# Schematic_LED_Board.net
KiCad netlist of a schematic drawn in EAGLE
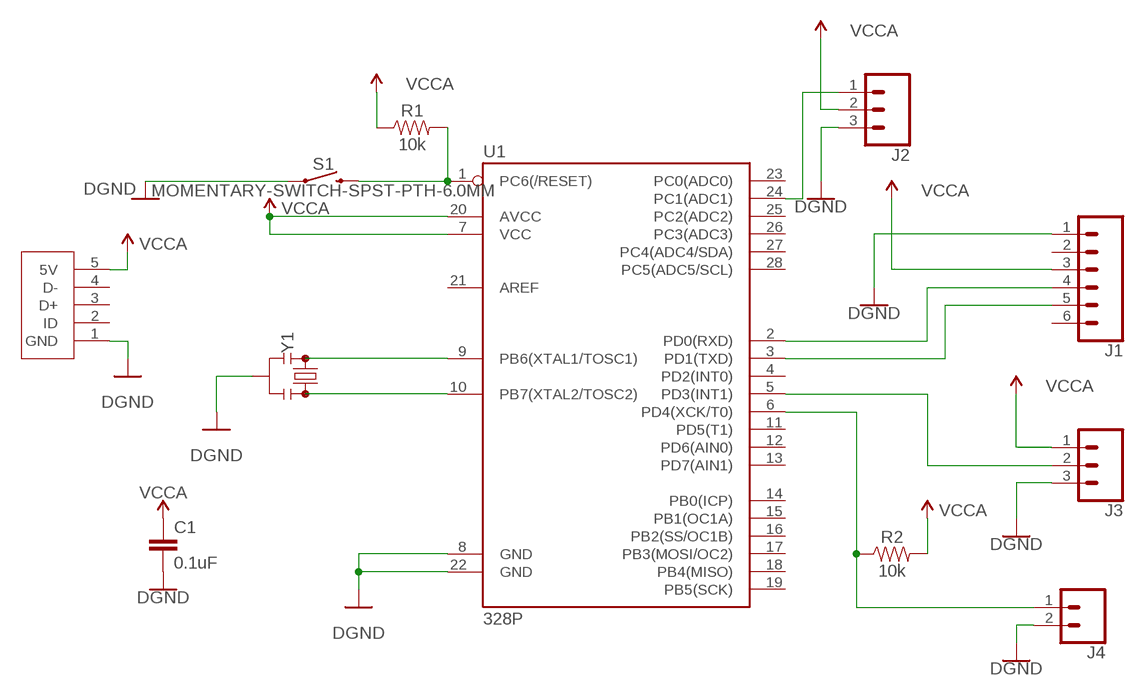
[diagram p0: schematic, sheet 1]

(export (version "E")
  (design (tool "Eeschema 10.0.6"))
  (components
    (comp (ref "C1")
      (value "0.1uF")
      (footprint "eagle-import:CAP-PTH-SMALL-KIT")
      (libsource (lib "eagle-import") (part "0.1UF-KIT-EZ-50V-20%"))
    )
    (comp (ref "J1")
      (value "CONN_06LONGPADS")
      (footprint "eagle-import:1X06_LONGPADS")
      (libsource (lib "eagle-import") (part "CONN_06LONGPADS"))
    )
    (comp (ref "J2")
      (value "CONN_03LONGPADS")
      (footprint "eagle-import:1X03_LONGPADS")
      (libsource (lib "eagle-import") (part "CONN_03LONGPADS"))
    )
    (comp (ref "J3")
      (value "CONN_03LONGPADS")
      (footprint "eagle-import:1X03_LONGPADS")
      (libsource (lib "eagle-import") (part "CONN_03LONGPADS"))
    )
    (comp (ref "J4")
      (value "CONN_02PTH3")
      (footprint "eagle-import:1X02_LONGPADS")
      (libsource (lib "eagle-import") (part "CONN_02PTH3"))
    )
    (comp (ref "R1")
      (value "10k")
      (footprint "eagle-import:AXIAL-0.3")
      (libsource (lib "eagle-import") (part "10KOHM-HORIZ-1/6W-5%"))
    )
    (comp (ref "R2")
      (value "10k")
      (footprint "eagle-import:AXIAL-0.3")
      (libsource (lib "eagle-import") (part "10KOHM-HORIZ-1/6W-5%"))
    )
    (comp (ref "S1")
      (value "MOMENTARY-SWITCH-SPST-PTH-6.0MM")
      (footprint "eagle-import:TACTILE_SWITCH_PTH_6.0MM")
      (libsource (lib "eagle-import") (part "MOMENTARY-SWITCH-SPST-PTH-6.0MM"))
    )
    (comp (ref "U$8")
      (value "USBPOWER")
      (footprint "eagle-import:1X05_LONGPADS")
      (libsource (lib "eagle-import") (part "USBPOWER"))
    )
    (comp (ref "U1")
      (value "328P")
      (footprint "eagle-import:DIP28")
      (libsource (lib "eagle-import") (part "ATMEGA328P_PDIP"))
    )
    (comp (ref "Y1")
      (value "RESONATORPTH-7.6X3.8")
      (footprint "eagle-import:RESONATOR-PTH-7.6X3.8")
      (libsource (lib "eagle-import") (part "RESONATORPTH-7.6X3.8"))
    )
  )
  (nets
    (net (code "1") (name "DGND") (class "Default")
      (node (ref "C1") (pin "2") (pinfunction "2_2") (pintype "passive"))
      (node (ref "J1") (pin "1") (pinfunction "1_1") (pintype "passive"))
      (node (ref "J2") (pin "3") (pinfunction "3_3") (pintype "passive"))
      (node (ref "J3") (pin "3") (pinfunction "3_3") (pintype "passive"))
      (node (ref "J4") (pin "2") (pinfunction "2_2") (pintype "passive"))
      (node (ref "S1") (pin "1") (pinfunction "1_1") (pintype "passive"))
      (node (ref "U$8") (pin "1") (pinfunction "GND_1") (pintype "bidirectional"))
      (node (ref "U1") (pin "22") (pinfunction "GND_22") (pintype "bidirectional"))
      (node (ref "U1") (pin "8") (pinfunction "GND_8") (pintype "bidirectional"))
      (node (ref "Y1") (pin "2") (pinfunction "2_2") (pintype "passive"))
    )
    (net (code "2") (name "Net-(R1-2)") (class "Default")
      (node (ref "R1") (pin "P$2") (pinfunction "2_P$2") (pintype "passive"))
      (node (ref "S1") (pin "3") (pinfunction "2_3") (pintype "passive"))
      (node (ref "U1") (pin "1") (pinfunction "PC6(/RESET)_1") (pintype "bidirectional"))
    )
    (net (code "3") (name "Net-(R2-1)") (class "Default")
      (node (ref "J4") (pin "1") (pinfunction "1_1") (pintype "passive"))
      (node (ref "R2") (pin "P$1") (pinfunction "1_P$1") (pintype "passive"))
      (node (ref "U1") (pin "6") (pinfunction "PD4(XCK/T0)_6") (pintype "bidirectional"))
    )
    (net (code "4") (name "Net-(U1-PB6(XTAL1{slash}TOSC1))") (class "Default")
      (node (ref "U1") (pin "9") (pinfunction "PB6(XTAL1/TOSC1)_9") (pintype "bidirectional"))
      (node (ref "Y1") (pin "1") (pinfunction "1_1") (pintype "passive"))
    )
    (net (code "5") (name "Net-(U1-PB7(XTAL2{slash}TOSC2))") (class "Default")
      (node (ref "U1") (pin "10") (pinfunction "PB7(XTAL2/TOSC2)_10") (pintype "bidirectional"))
      (node (ref "Y1") (pin "3") (pinfunction "3_3") (pintype "passive"))
    )
    (net (code "6") (name "Net-(U1-PC1(ADC1))") (class "Default")
      (node (ref "J2") (pin "1") (pinfunction "1_1") (pintype "passive"))
      (node (ref "U1") (pin "24") (pinfunction "PC1(ADC1)_24") (pintype "bidirectional"))
    )
    (net (code "7") (name "Net-(U1-PD0(RXD))") (class "Default")
      (node (ref "J1") (pin "4") (pinfunction "4_4") (pintype "passive"))
      (node (ref "U1") (pin "2") (pinfunction "PD0(RXD)_2") (pintype "bidirectional"))
    )
    (net (code "8") (name "Net-(U1-PD1(TXD))") (class "Default")
      (node (ref "J1") (pin "5") (pinfunction "5_5") (pintype "passive"))
      (node (ref "U1") (pin "3") (pinfunction "PD1(TXD)_3") (pintype "bidirectional"))
    )
    (net (code "9") (name "Net-(U1-PD3(INT1))") (class "Default")
      (node (ref "J3") (pin "2") (pinfunction "2_2") (pintype "passive"))
      (node (ref "U1") (pin "5") (pinfunction "PD3(INT1)_5") (pintype "bidirectional"))
    )
    (net (code "10") (name "VCCA") (class "Default")
      (node (ref "C1") (pin "1") (pinfunction "1_1") (pintype "passive"))
      (node (ref "J1") (pin "3") (pinfunction "3_3") (pintype "passive"))
      (node (ref "J2") (pin "2") (pinfunction "2_2") (pintype "passive"))
      (node (ref "J3") (pin "1") (pinfunction "1_1") (pintype "passive"))
      (node (ref "R1") (pin "P$1") (pinfunction "1_P$1") (pintype "passive"))
      (node (ref "R2") (pin "P$2") (pinfunction "2_P$2") (pintype "passive"))
      (node (ref "U$8") (pin "5") (pinfunction "5V_5") (pintype "bidirectional"))
      (node (ref "U1") (pin "20") (pinfunction "AVCC_20") (pintype "bidirectional"))
      (node (ref "U1") (pin "7") (pinfunction "VCC_7") (pintype "bidirectional"))
    )
    (net (code "11") (name "unconnected-(J1-Pad2)") (class "Default")
      (node (ref "J1") (pin "2") (pinfunction "2_2") (pintype "passive"))
    )
    (net (code "12") (name "unconnected-(J1-Pad6)") (class "Default")
      (node (ref "J1") (pin "6") (pinfunction "6_6") (pintype "passive"))
    )
    (net (code "13") (name "unconnected-(U$8-D+-Pad3)") (class "Default")
      (node (ref "U$8") (pin "3") (pinfunction "D+_3") (pintype "bidirectional"))
    )
    (net (code "14") (name "unconnected-(U$8-D--Pad4)") (class "Default")
      (node (ref "U$8") (pin "4") (pinfunction "D-_4") (pintype "bidirectional"))
    )
    (net (code "15") (name "unconnected-(U$8-ID-Pad2)") (class "Default")
      (node (ref "U$8") (pin "2") (pinfunction "ID_2") (pintype "bidirectional"))
    )
    (net (code "16") (name "unconnected-(U1-AREF-Pad21)") (class "Default")
      (node (ref "U1") (pin "21") (pinfunction "AREF_21") (pintype "bidirectional"))
    )
    (net (code "17") (name "unconnected-(U1-PB0(ICP)-Pad14)") (class "Default")
      (node (ref "U1") (pin "14") (pinfunction "PB0(ICP)_14") (pintype "bidirectional"))
    )
    (net (code "18") (name "unconnected-(U1-PB1(OC1A)-Pad15)") (class "Default")
      (node (ref "U1") (pin "15") (pinfunction "PB1(OC1A)_15") (pintype "bidirectional"))
    )
    (net (code "19") (name "unconnected-(U1-PB2(SS{slash}OC1B)-Pad16)") (class "Default")
      (node (ref "U1") (pin "16") (pinfunction "PB2(SS/OC1B)_16") (pintype "bidirectional"))
    )
    (net (code "20") (name "unconnected-(U1-PB3(MOSI{slash}OC2)-Pad17)") (class "Default")
      (node (ref "U1") (pin "17") (pinfunction "PB3(MOSI/OC2)_17") (pintype "bidirectional"))
    )
    (net (code "21") (name "unconnected-(U1-PB4(MISO)-Pad18)") (class "Default")
      (node (ref "U1") (pin "18") (pinfunction "PB4(MISO)_18") (pintype "bidirectional"))
    )
    (net (code "22") (name "unconnected-(U1-PB5(SCK)-Pad19)") (class "Default")
      (node (ref "U1") (pin "19") (pinfunction "PB5(SCK)_19") (pintype "bidirectional"))
    )
    (net (code "23") (name "unconnected-(U1-PC0(ADC0)-Pad23)") (class "Default")
      (node (ref "U1") (pin "23") (pinfunction "PC0(ADC0)_23") (pintype "bidirectional"))
    )
    (net (code "24") (name "unconnected-(U1-PC2(ADC2)-Pad25)") (class "Default")
      (node (ref "U1") (pin "25") (pinfunction "PC2(ADC2)_25") (pintype "bidirectional"))
    )
    (net (code "25") (name "unconnected-(U1-PC3(ADC3)-Pad26)") (class "Default")
      (node (ref "U1") (pin "26") (pinfunction "PC3(ADC3)_26") (pintype "bidirectional"))
    )
    (net (code "26") (name "unconnected-(U1-PC4(ADC4{slash}SDA)-Pad27)") (class "Default")
      (node (ref "U1") (pin "27") (pinfunction "PC4(ADC4/SDA)_27") (pintype "bidirectional"))
    )
    (net (code "27") (name "unconnected-(U1-PC5(ADC5{slash}SCL)-Pad28)") (class "Default")
      (node (ref "U1") (pin "28") (pinfunction "PC5(ADC5/SCL)_28") (pintype "bidirectional"))
    )
    (net (code "28") (name "unconnected-(U1-PD2(INT0)-Pad4)") (class "Default")
      (node (ref "U1") (pin "4") (pinfunction "PD2(INT0)_4") (pintype "bidirectional"))
    )
    (net (code "29") (name "unconnected-(U1-PD5(T1)-Pad11)") (class "Default")
      (node (ref "U1") (pin "11") (pinfunction "PD5(T1)_11") (pintype "bidirectional"))
    )
    (net (code "30") (name "unconnected-(U1-PD6(AIN0)-Pad12)") (class "Default")
      (node (ref "U1") (pin "12") (pinfunction "PD6(AIN0)_12") (pintype "bidirectional"))
    )
    (net (code "31") (name "unconnected-(U1-PD7(AIN1)-Pad13)") (class "Default")
      (node (ref "U1") (pin "13") (pinfunction "PD7(AIN1)_13") (pintype "bidirectional"))
    )
  )
)
